# synth-zodiac-sagittarius-speaker.net
KiCad netlist of a schematic drawn in EAGLE
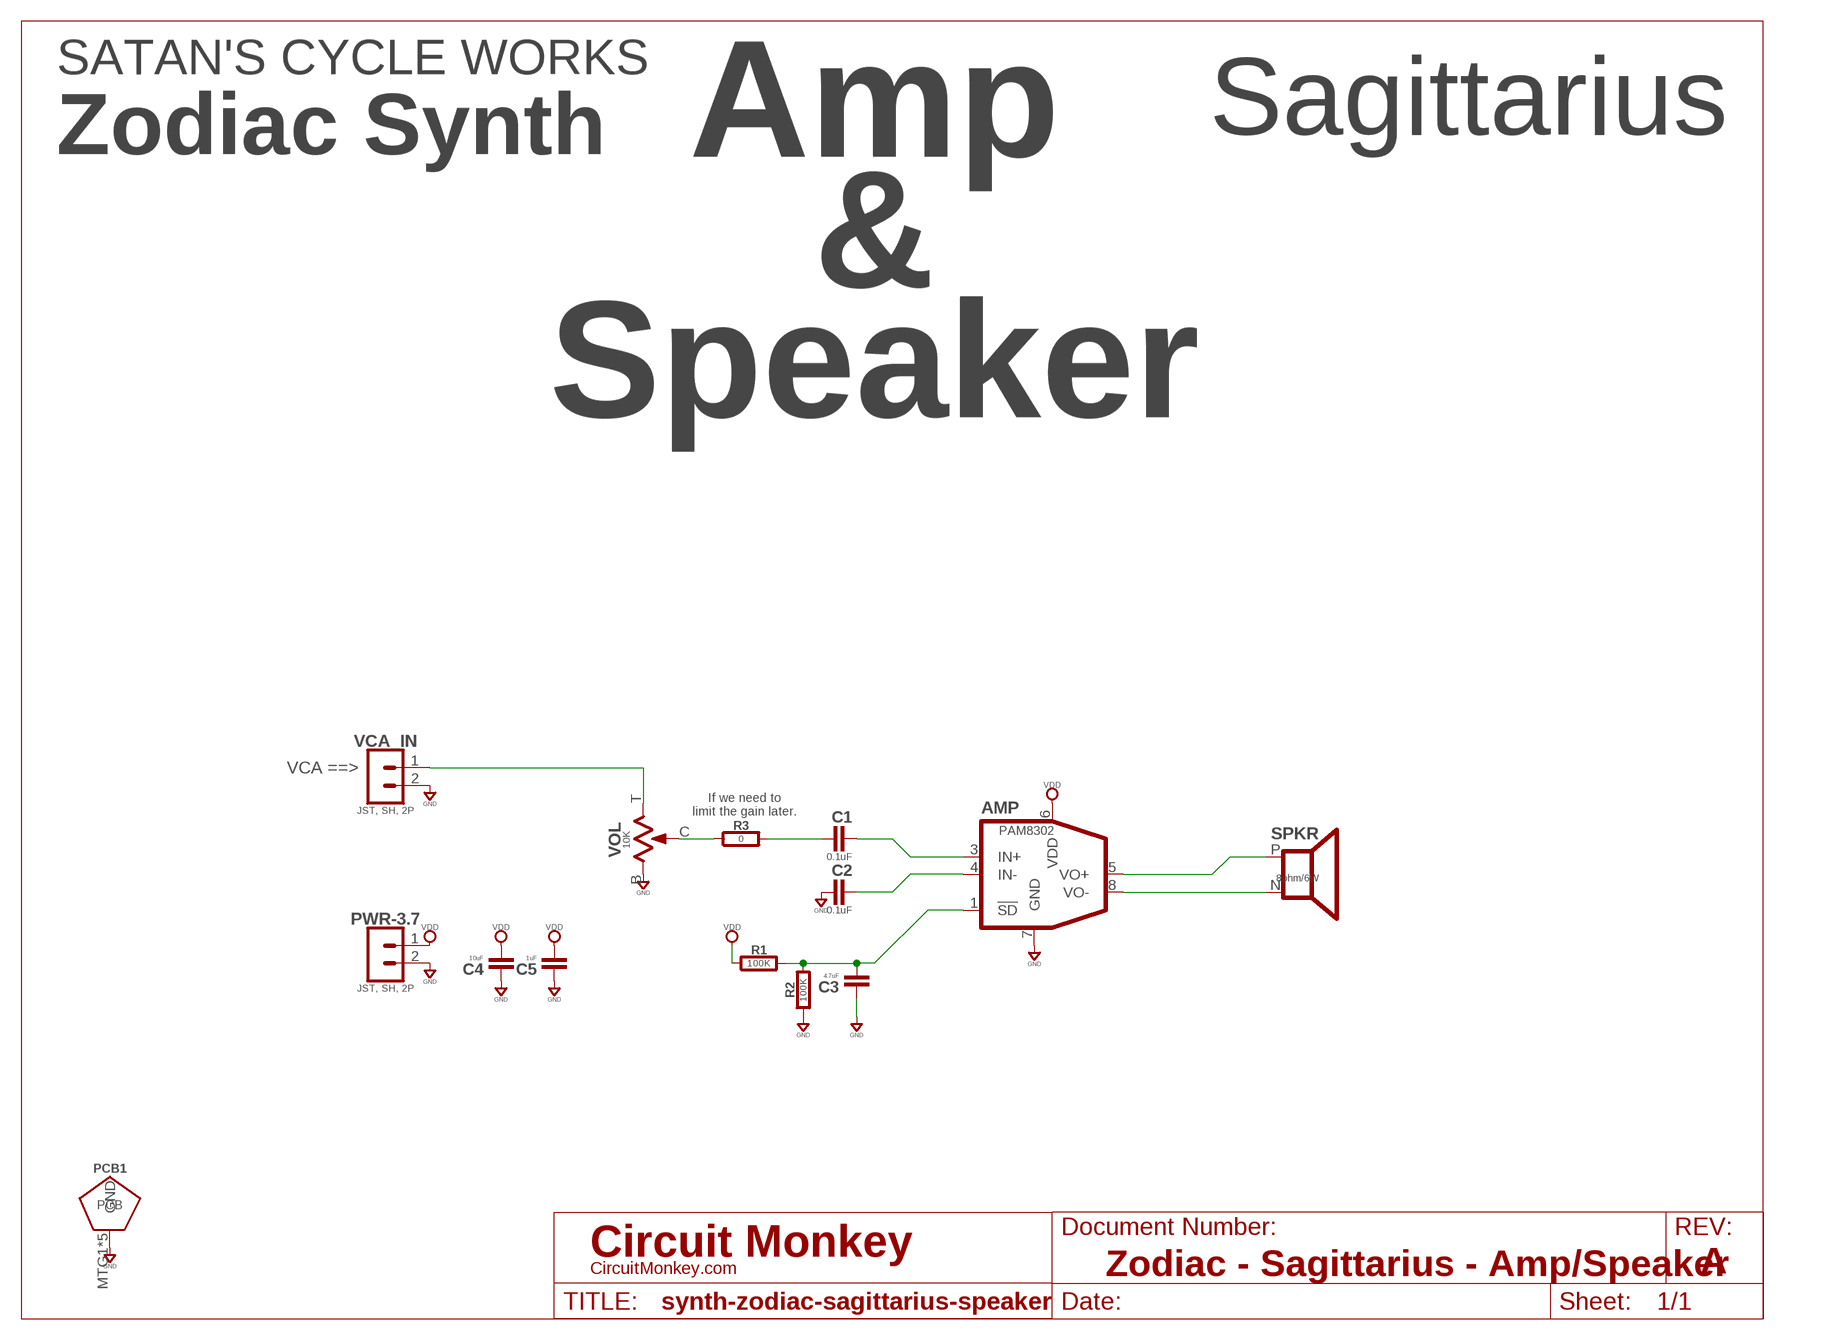
[diagram p0: schematic, sheet 1]

(export (version "E")
  (design (tool "Eeschema 10.0.6"))
  (components
    (comp (ref "AMP")
      (value "PAM8302")
      (footprint "eagle-import:U-DFN3030-8")
      (fields (field (name "MFR") "Diodes, Inc.") (field (name "MPN") "PAM8302AAYC"))
      (libsource (lib "eagle-import") (part "PAM8302-DFN"))
    )
    (comp (ref "C1")
      (value "0.1uF")
      (footprint "eagle-import:0603-CAP")
      (libsource (lib "eagle-import") (part "CAPACITOR0603"))
    )
    (comp (ref "C2")
      (value "0.1uF")
      (footprint "eagle-import:0603-CAP")
      (libsource (lib "eagle-import") (part "CAPACITOR0603"))
    )
    (comp (ref "C3")
      (value "4.7uF")
      (footprint "eagle-import:0603-CAP")
      (libsource (lib "eagle-import") (part "CAPACITOR0603"))
    )
    (comp (ref "C4")
      (value "10uF")
      (footprint "eagle-import:0603-CAP")
      (libsource (lib "eagle-import") (part "CAPACITOR0603"))
    )
    (comp (ref "C5")
      (value "1uF")
      (footprint "eagle-import:0603-CAP")
      (libsource (lib "eagle-import") (part "CAPACITOR0603"))
    )
    (comp (ref "PCB1")
      (value "PCB FAB")
      (footprint "eagle-import:PENTAGON-40MM-RAD")
      (libsource (lib "eagle-import") (part "PENTAGON-40R"))
    )
    (comp (ref "PWR-3.7")
      (value "JST, SH, 2P")
      (footprint "eagle-import:BM02B-SRSS-TB")
      (fields (field (name "MFR") "JST") (field (name "MPN") "BMB02B-SRSS-TB"))
      (libsource (lib "eagle-import") (part "02P-SM-VT-SMT"))
    )
    (comp (ref "R1")
      (value "100K")
      (footprint "eagle-import:0603-RES")
      (libsource (lib "eagle-import") (part "RESISTOR0603"))
    )
    (comp (ref "R2")
      (value "100K")
      (footprint "eagle-import:0603-RES")
      (libsource (lib "eagle-import") (part "RESISTOR0603"))
    )
    (comp (ref "R3")
      (value "0")
      (footprint "eagle-import:0603-RES")
      (libsource (lib "eagle-import") (part "RESISTOR0603"))
    )
    (comp (ref "SPKR")
      (value "8ohm/6W")
      (footprint "eagle-import:SPKR-40X30")
      (fields (field (name "MFR") "CUI") (field (name "MPN") "CDS-40288"))
      (libsource (lib "eagle-import") (part "SPEAKER-40X30-PADS-SMT"))
    )
    (comp (ref "VCA_IN")
      (value "JST, SH, 2P")
      (footprint "eagle-import:BM02B-SRSS-TB")
      (fields (field (name "MFR") "JST") (field (name "MPN") "BMB02B-SRSS-TB"))
      (libsource (lib "eagle-import") (part "02P-SM-VT-SMT"))
    )
    (comp (ref "VOL")
      (value "10K")
      (footprint "eagle-import:POT-RV9110")
      (fields (field (name "MFR") "Tayda") (field (name "MPN") "RV9110NO-OS15A00"))
      (libsource (lib "eagle-import") (part "TRIMPOT9MM_PCB_SHAFT"))
    )
  )
  (nets
    (net (code "1") (name "GND") (class "Default")
      (node (ref "AMP") (pin "7") (pinfunction "GND_7") (pintype "bidirectional"))
      (node (ref "C2") (pin "1") (pinfunction "1_1") (pintype "passive"))
      (node (ref "C3") (pin "1") (pinfunction "1_1") (pintype "passive"))
      (node (ref "C4") (pin "1") (pinfunction "1_1") (pintype "passive"))
      (node (ref "C5") (pin "1") (pinfunction "1_1") (pintype "passive"))
      (node (ref "PCB1") (pin "MTG1") (pinfunction "GND_MTG1") (pintype "bidirectional"))
      (node (ref "PCB1") (pin "MTG2") (pinfunction "GND_MTG2") (pintype "bidirectional"))
      (node (ref "PCB1") (pin "MTG3") (pinfunction "GND_MTG3") (pintype "bidirectional"))
      (node (ref "PCB1") (pin "MTG4") (pinfunction "GND_MTG4") (pintype "bidirectional"))
      (node (ref "PCB1") (pin "MTG5") (pinfunction "GND_MTG5") (pintype "bidirectional"))
      (node (ref "PWR-3.7") (pin "2") (pinfunction "2_2") (pintype "passive"))
      (node (ref "R2") (pin "1") (pinfunction "1_1") (pintype "passive"))
      (node (ref "VCA_IN") (pin "2") (pinfunction "2_2") (pintype "passive"))
      (node (ref "VOL") (pin "B") (pinfunction "1_B") (pintype "passive"))
    )
    (net (code "2") (name "Net-(AMP-IN+)") (class "Default")
      (node (ref "AMP") (pin "3") (pinfunction "IN+_3") (pintype "bidirectional"))
      (node (ref "C1") (pin "2") (pinfunction "2_2") (pintype "passive"))
    )
    (net (code "3") (name "Net-(AMP-IN-)") (class "Default")
      (node (ref "AMP") (pin "4") (pinfunction "IN-_4") (pintype "bidirectional"))
      (node (ref "C2") (pin "2") (pinfunction "2_2") (pintype "passive"))
    )
    (net (code "4") (name "Net-(AMP-VO+)") (class "Default")
      (node (ref "AMP") (pin "5") (pinfunction "VO+_5") (pintype "bidirectional"))
      (node (ref "SPKR") (pin "P") (pinfunction "+_P") (pintype "bidirectional"))
    )
    (net (code "5") (name "Net-(AMP-VO-)") (class "Default")
      (node (ref "AMP") (pin "8") (pinfunction "VO-_8") (pintype "bidirectional"))
      (node (ref "SPKR") (pin "N") (pinfunction "-_N") (pintype "bidirectional"))
    )
    (net (code "6") (name "Net-(AMP-~{SD})") (class "Default")
      (node (ref "AMP") (pin "1") (pinfunction "~{SD}_1") (pintype "bidirectional"))
      (node (ref "C3") (pin "2") (pinfunction "2_2") (pintype "passive"))
      (node (ref "R1") (pin "2") (pinfunction "2_2") (pintype "passive"))
      (node (ref "R2") (pin "2") (pinfunction "2_2") (pintype "passive"))
    )
    (net (code "7") (name "Net-(C1-Pad1)") (class "Default")
      (node (ref "C1") (pin "1") (pinfunction "1_1") (pintype "passive"))
      (node (ref "R3") (pin "2") (pinfunction "2_2") (pintype "passive"))
    )
    (net (code "8") (name "Net-(VOL-2)") (class "Default")
      (node (ref "R3") (pin "1") (pinfunction "1_1") (pintype "passive"))
      (node (ref "VOL") (pin "C") (pinfunction "2_C") (pintype "passive"))
    )
    (net (code "9") (name "Net-(VOL-3)") (class "Default")
      (node (ref "VCA_IN") (pin "1") (pinfunction "1_1") (pintype "passive"))
      (node (ref "VOL") (pin "T") (pinfunction "3_T") (pintype "passive"))
    )
    (net (code "10") (name "VDD") (class "Default")
      (node (ref "AMP") (pin "6") (pinfunction "VDD_6") (pintype "bidirectional"))
      (node (ref "C4") (pin "2") (pinfunction "2_2") (pintype "passive"))
      (node (ref "C5") (pin "2") (pinfunction "2_2") (pintype "passive"))
      (node (ref "PWR-3.7") (pin "1") (pinfunction "1_1") (pintype "passive"))
      (node (ref "R1") (pin "1") (pinfunction "1_1") (pintype "passive"))
    )
  )
)
